# 14871_Schematic.net
KiCad netlist of a schematic drawn in Altium Designer
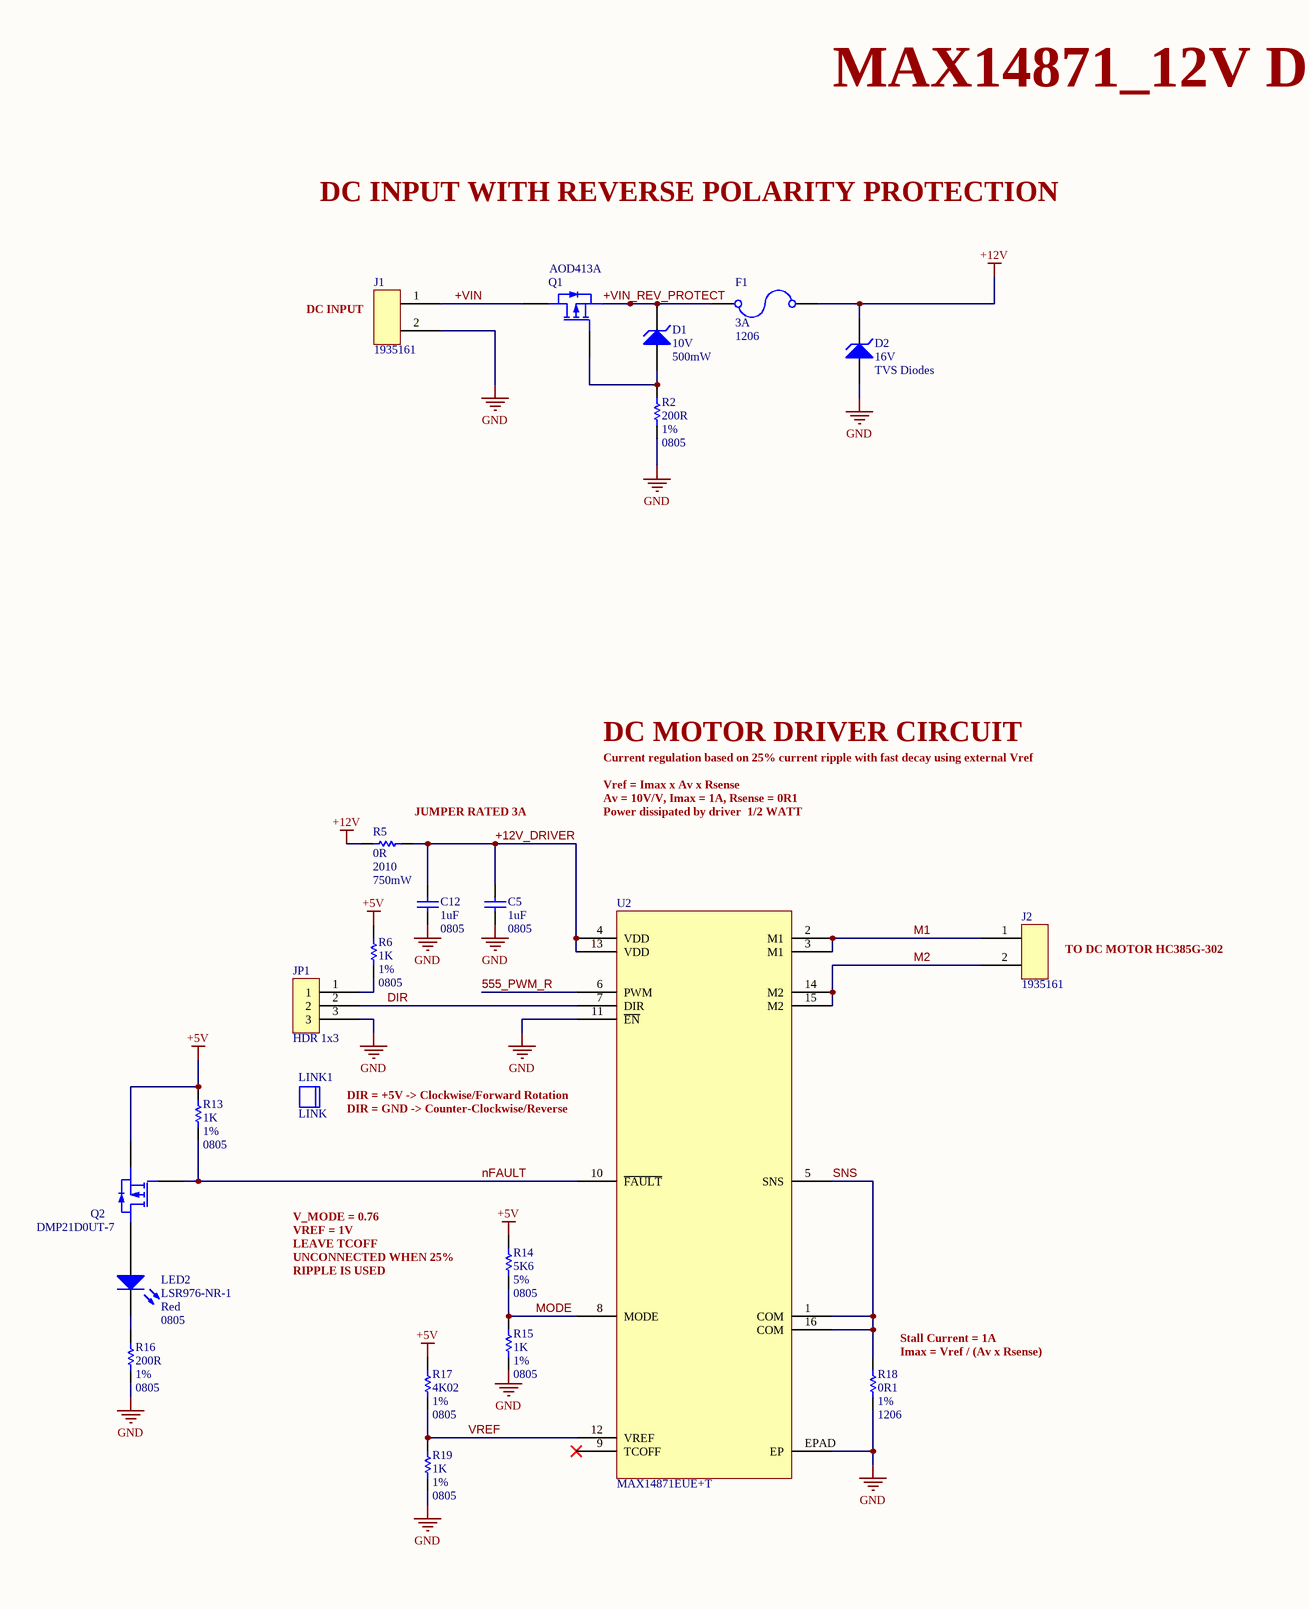
[diagram p0: 14871_Schematic.SchDoc, left]
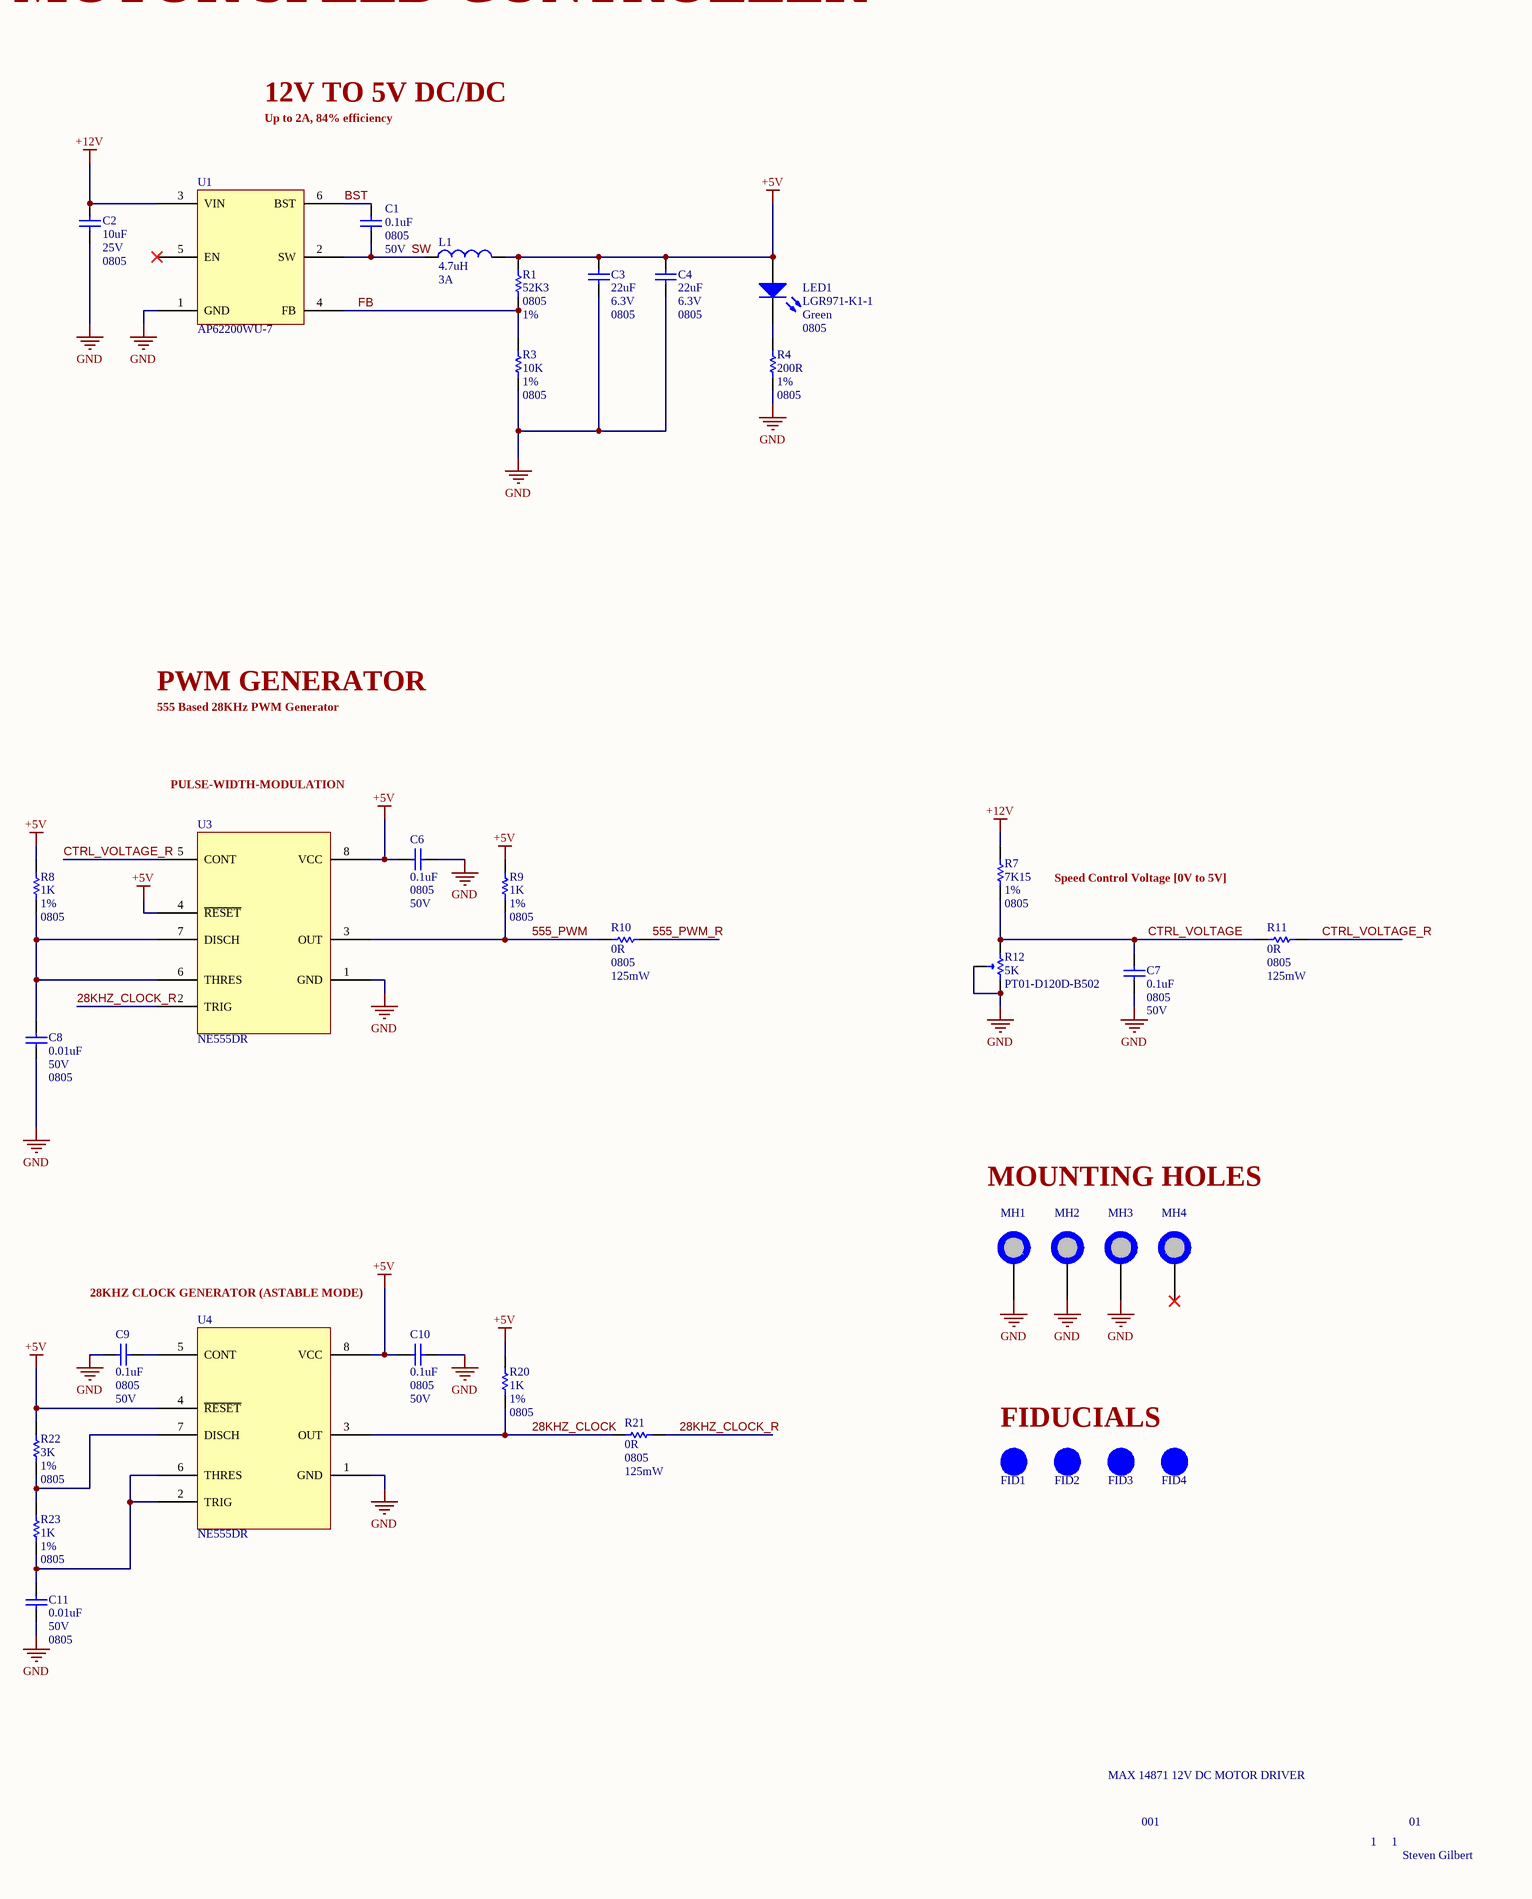
[diagram p1: 14871_Schematic.SchDoc, right]

(export (version "E")
  (design (tool "Eeschema 10.0.6"))
  (components
    (comp (ref "C1")
      (value "0.1uF")
      (footprint "C0805")
      (description "CAP CER 0.1UF X7R 50V 0805  +/-10%; 50WVDC; SMD; 2.5% Df; 0.037IN. ,")
      (fields
        (field (name "MANUFACTURER") "Kyocera AVX")
        (field (name "MANUFACTURER PART NUMBER") "08055C104KAT2A")
        (field (name "CASE CODE (IMPERIAL)") "0805")
        (field (name "VOLTAGE RATING (DC)") "50V")
      )
      (libsource (lib "MAX14871_Project") (part "08055C104KAT2A"))
    )
    (comp (ref "C2")
      (value "10uF")
      (footprint "C0805")
      (description "CAP CER 10UF 25V X5R 0805")
      (fields
        (field (name "MANUFACTURER") "Murata")
        (field (name "MANUFACTURER PART NUMBER") "GRM21BR61E106KA73L")
        (field (name "VOLTAGE RATING (DC)") "25V")
        (field (name "CASE/PACKAGE") "0805")
      )
      (libsource (lib "MAX14871_Project") (part "GRM21BR61E106KA73L"))
    )
    (comp (ref "C3")
      (value "22uF")
      (footprint "C0805")
      (description "CAP CER 6.3V X5R 20% SMD 0805 85°C Embossed T/R")
      (fields
        (field (name "MANUFACTURER") "Samsung")
        (field (name "MANUFACTURER PART NUMBER") "CL21A226MQQNNNG")
        (field (name "VOLTAGE RATING") "6.3V")
        (field (name "CASE/PACKAGE") "0805")
      )
      (libsource (lib "MAX14871_Project") (part "CL21A226MQQNNNG"))
    )
    (comp (ref "C4")
      (value "22uF")
      (footprint "C0805")
      (description "CAP CER 6.3V X5R 20% SMD 0805 85°C Embossed T/R")
      (fields
        (field (name "MANUFACTURER") "Samsung")
        (field (name "MANUFACTURER PART NUMBER") "CL21A226MQQNNNG")
        (field (name "VOLTAGE RATING") "6.3V")
        (field (name "CASE/PACKAGE") "0805")
      )
      (libsource (lib "MAX14871_Project") (part "CL21A226MQQNNNG"))
    )
    (comp (ref "C5")
      (value "1uF")
      (footprint "C0805")
      (description "Cap Cer 1UF 35V X7R 0805")
      (fields
        (field (name "MANUFACTURER") "Kyocera AVX")
        (field (name "MANUFACTURER PART NUMBER") "0805DC105KAT2A")
        (field (name "CASE/PACKAGE") "0805")
      )
      (libsource (lib "MAX14871_Project") (part "0805DC105KAT2A"))
    )
    (comp (ref "C6")
      (value "0.1uF")
      (footprint "C0805")
      (description "CAP CER 0.1UF X7R 50V 0805  +/-10%; 50WVDC; SMD; 2.5% Df; 0.037IN. ,")
      (fields
        (field (name "MANUFACTURER") "Kyocera AVX")
        (field (name "MANUFACTURER PART NUMBER") "08055C104KAT2A")
        (field (name "CASE CODE (IMPERIAL)") "0805")
        (field (name "VOLTAGE RATING (DC)") "50V")
      )
      (libsource (lib "MAX14871_Project") (part "08055C104KAT2A"))
    )
    (comp (ref "C7")
      (value "0.1uF")
      (footprint "C0805")
      (description "CAP CER 0.1UF X7R 50V 0805  +/-10%; 50WVDC; SMD; 2.5% Df; 0.037IN. ,")
      (fields
        (field (name "MANUFACTURER") "Kyocera AVX")
        (field (name "MANUFACTURER PART NUMBER") "08055C104KAT2A")
        (field (name "CASE CODE (IMPERIAL)") "0805")
        (field (name "VOLTAGE RATING (DC)") "50V")
      )
      (libsource (lib "MAX14871_Project") (part "08055C104KAT2A"))
    )
    (comp (ref "C8")
      (value "0.01uF")
      (footprint "C0805")
      (description "CAP CER 0.01uF 50V X7R 10% SMD 0805 125C Plastic T/R")
      (fields
        (field (name "MANUFACTURER") "KEMET")
        (field (name "MANUFACTURER PART NUMBER") "C0805C103K5RACTU")
        (field (name "VOLTAGE RATING") "50V")
        (field (name "CASE/PACKAGE") "0805")
      )
      (libsource (lib "MAX14871_Project") (part "C0805C103K5RACTU"))
    )
    (comp (ref "C9")
      (value "0.1uF")
      (footprint "C0805")
      (description "CAP CER 0.1UF X7R 50V 0805  +/-10%; 50WVDC; SMD; 2.5% Df; 0.037IN. ,")
      (fields
        (field (name "MANUFACTURER") "Kyocera AVX")
        (field (name "MANUFACTURER PART NUMBER") "08055C104KAT2A")
        (field (name "CASE CODE (IMPERIAL)") "0805")
        (field (name "VOLTAGE RATING (DC)") "50V")
      )
      (libsource (lib "MAX14871_Project") (part "08055C104KAT2A"))
    )
    (comp (ref "C10")
      (value "0.1uF")
      (footprint "C0805")
      (description "CAP CER 0.1UF X7R 50V 0805  +/-10%; 50WVDC; SMD; 2.5% Df; 0.037IN. ,")
      (fields
        (field (name "MANUFACTURER") "Kyocera AVX")
        (field (name "MANUFACTURER PART NUMBER") "08055C104KAT2A")
        (field (name "CASE CODE (IMPERIAL)") "0805")
        (field (name "VOLTAGE RATING (DC)") "50V")
      )
      (libsource (lib "MAX14871_Project") (part "08055C104KAT2A"))
    )
    (comp (ref "C11")
      (value "0.01uF")
      (footprint "C0805")
      (description "CAP CER 0.01uF 50V X7R 10% SMD 0805 125C Plastic T/R")
      (fields
        (field (name "MANUFACTURER") "KEMET")
        (field (name "MANUFACTURER PART NUMBER") "C0805C103K5RACTU")
        (field (name "VOLTAGE RATING") "50V")
        (field (name "CASE/PACKAGE") "0805")
      )
      (libsource (lib "MAX14871_Project") (part "C0805C103K5RACTU"))
    )
    (comp (ref "C12")
      (value "1uF")
      (footprint "C0805")
      (description "Cap Cer 1UF 35V X7R 0805")
      (fields
        (field (name "MANUFACTURER") "Kyocera AVX")
        (field (name "MANUFACTURER PART NUMBER") "0805DC105KAT2A")
        (field (name "CASE/PACKAGE") "0805")
      )
      (libsource (lib "MAX14871_Project") (part "0805DC105KAT2A"))
    )
    (comp (ref "D1")
      (value "10V")
      (footprint "SOD123_Zener")
      (description "Vz=10V 9.4V~10.6V Izt=5mA")
      (fields
        (field (name "MANUFACTURER") "Diodes")
        (field (name "TOLERANCE") "6%")
        (field (name "MAX POWER DISSIPATION") "500mW")
      )
      (libsource (lib "MAX14871_Project") (part "BZT52C10-7-F"))
    )
    (comp (ref "D2")
      (value "16V")
      (footprint "TVS_SOD123FL")
      (description "TVS DIODE 16VWM 26VC SOD123FL")
      (fields
        (field (name "MANUFACTURER") "MCC")
        (field (name "MANUFACTURER PART NUMBER") "SMF16A-TP")
        (field (name "CATEGORY") "TVS Diodes")
      )
      (libsource (lib "MAX14871_Project") (part "SMF16A-TP"))
    )
    (comp (ref "F1")
      (value "3A")
      (footprint "FUSE1206")
      (description "Fuse Chip 3A 63V Slow Blow 2-Pin T/R")
      (fields
        (field (name "MANUFACTURER") "Bel")
        (field (name "MANUFACTURER PART NUMBER") "0685T3000-01")
        (field (name "CASE/PACKAGE") "1206")
      )
      (libsource (lib "MAX14871_Project") (part "0685T3000-01"))
    )
    (comp (ref "FID1")
      (value "FID_1MM")
      (footprint "FID_40X120D")
      (description "Fiducial 40mil diameter, 120 Mask")
      (libsource (lib "MAX14871_Project") (part "FID_1mm"))
    )
    (comp (ref "FID2")
      (value "FID_1MM")
      (footprint "FID_40X120D")
      (description "Fiducial 40mil diameter, 120 Mask")
      (libsource (lib "MAX14871_Project") (part "FID_1mm"))
    )
    (comp (ref "FID3")
      (value "FID_1MM")
      (footprint "FID_40X120D")
      (description "Fiducial 40mil diameter, 120 Mask")
      (libsource (lib "MAX14871_Project") (part "FID_1mm"))
    )
    (comp (ref "FID4")
      (value "FID_1MM")
      (footprint "FID_40X120D")
      (description "Fiducial 40mil diameter, 120 Mask")
      (libsource (lib "MAX14871_Project") (part "FID_1mm"))
    )
    (comp (ref "J1")
      (value "1935161")
      (footprint "1935161")
      (description "Conn PC Terminal Block 2 POS 5mm Solder ST Thru-Hole 17.5A")
      (fields (field (name "MANUFACTURER") "Phoenix Contact") (field (name "VOLTAGE") "300V"))
      (libsource (lib "MAX14871_Project") (part "1935161"))
    )
    (comp (ref "J2")
      (value "1935161")
      (footprint "1935161")
      (description "Conn PC Terminal Block 2 POS 5mm Solder ST Thru-Hole 17.5A")
      (fields (field (name "MANUFACTURER") "Phoenix Contact") (field (name "VOLTAGE") "300V"))
      (libsource (lib "") (part "1935161_1"))
    )
    (comp (ref "JP1")
      (value "HDR 1x3")
      (footprint "HDR_1x3_2.54mm")
      (description "CONN HEADER VERT 3POS 2.54MM")
      (libsource (lib "MAX14871_Project") (part "68000-103HLF"))
    )
    (comp (ref "L1")
      (value "4.7uH")
      (footprint "NR6028T4R7M")
      (description "Inductor Power Shielded Wirewound 4.7uH 20% 100KHz Ferrite 3A 0.0403Ohm DCR 2424 T/R")
      (fields
        (field (name "MANUFACTURER") "Taiyo Yuden")
        (field (name "MANUFACTURER PART NUMBER") "NR6028T4R7M")
        (field (name "MAX DC CURRENT") "3A")
      )
      (libsource (lib "MAX14871_Project") (part "NR6028T4R7M"))
    )
    (comp (ref "LED1")
      (value "LGR971-K1-1")
      (footprint "LED0805 - Green")
      (description "LED SMT GREEN 0805")
      (fields (field (name "ILLUMINATION COLOR") "Green") (field (name "CASE/PACKAGE") "0805"))
      (libsource (lib "MAX14871_Project") (part "LGR971-K1-1"))
    )
    (comp (ref "LED2")
      (value "LSR976-NR-1")
      (footprint "LED0805")
      (description "LED SMT RED 0805")
      (fields
        (field (name "MANUFACTURER") "Osram Opto")
        (field (name "ILLUMINATION COLOR") "Red")
        (field (name "CASE/PACKAGE") "0805")
      )
      (libsource (lib "MAX14871_Project") (part "LSR976-NR-1"))
    )
    (comp (ref "LINK1")
      (value "LINK")
      (description "2 Position 2.54 mm Centerline Single Circuit Open Top Jumper")
      (fields
        (field (name "MANUFACTURER") "Sullins")
        (field (name "MANUFACTURER PART NUMBER") "QPC02SXGN-RC")
      )
      (libsource (lib "MAX14871_Project") (part "QPC02SXGN-RC"))
    )
    (comp (ref "MH1")
      (value "MH_7.4MMC_3.2MMD")
      (footprint "MH_7.4MMC_3.2MMD")
      (description "Mounting Hole 7.4mm Diameter, 3.2mm Drill")
      (libsource (lib "MAX14871_Project") (part "MH_7.4MMC_3.2MMD"))
    )
    (comp (ref "MH2")
      (value "MH_7.4MMC_3.2MMD")
      (footprint "MH_7.4MMC_3.2MMD")
      (description "Mounting Hole 7.4mm Diameter, 3.2mm Drill")
      (libsource (lib "MAX14871_Project") (part "MH_7.4MMC_3.2MMD"))
    )
    (comp (ref "MH3")
      (value "MH_7.4MMC_3.2MMD")
      (footprint "MH_7.4MMC_3.2MMD")
      (description "Mounting Hole 7.4mm Diameter, 3.2mm Drill")
      (libsource (lib "MAX14871_Project") (part "MH_7.4MMC_3.2MMD"))
    )
    (comp (ref "MH4")
      (value "MH_7.4MMNC_3.2MMD")
      (footprint "MH_7.4MMD_3.2MMD_NON_COPPER_NPTH")
      (description "Hole 7.4MM Diameter (Non Copper), 3.2mm Drill NPTH")
      (libsource (lib "MAX14871_Project") (part "MH_7.4MMNC_3.2MMD"))
    )
    (comp (ref "Q1")
      (value "AOD413A")
      (footprint "TO252")
      (description "MOSFET P-CH 40V 12A TO252")
      (fields (field (name "MANUFACTURER") "Alpha & Omega Semiconductor"))
      (libsource (lib "MAX14871_Project") (part "AOD413A"))
    )
    (comp (ref "Q2")
      (value "DMP21D0UT-7")
      (footprint "SOT523")
      (description "MOSFET P-CH 20V 0.59A SOT523")
      (fields (field (name "MANUFACTURER") "Diodes"))
      (libsource (lib "MAX14871_Project") (part "DMP21D0UT-7"))
    )
    (comp (ref "R1")
      (value "52K3")
      (footprint "R0805")
      (description "RES SMD 52K3 OHM 1% 1/8W 0805 ±100ppm/°C SMD Paper T/R")
      (fields
        (field (name "MANUFACTURER") "Yageo")
        (field (name "MANUFACTURER PART NUMBER") "RC0805FR-0752K3L")
        (field (name "CASE/PACKAGE") "0805")
        (field (name "TOLERANCE") "1%")
      )
      (libsource (lib "MAX14871_Project") (part "RC0805FR-0752K3L"))
    )
    (comp (ref "R2")
      (value "200R")
      (footprint "R0805")
      (description "RES SMD 200 OHM 1% 1/8W 0805 ±100ppm/°C")
      (fields
        (field (name "MANUFACTURER") "Yageo")
        (field (name "MANUFACTURER PART NUMBER") "RC0805FR-07200RL")
        (field (name "TOLERANCE") "1%")
        (field (name "CASE/PACKAGE") "0805")
      )
      (libsource (lib "MAX14871_Project") (part "RC0805FR-07200RL"))
    )
    (comp (ref "R3")
      (value "10K")
      (footprint "R0805")
      (description "RES SMD 10K OHM 1% 1/8W  0805 Thick Film+/-100ppm/C Epoxy Pad SMD T/R")
      (fields
        (field (name "MANUFACTURER") "Yageo")
        (field (name "MANUFACTURER PART NUMBER") "RC0805FR-0710KL")
        (field (name "TOLERANCE") "1%")
        (field (name "CASE/PACKAGE") "0805")
      )
      (libsource (lib "MAX14871_Project") (part "RC0805FR-0710KL"))
    )
    (comp (ref "R4")
      (value "200R")
      (footprint "R0805")
      (description "RES SMD 200 OHM 1% 1/8W 0805 ±100ppm/°C")
      (fields
        (field (name "MANUFACTURER") "Yageo")
        (field (name "MANUFACTURER PART NUMBER") "RC0805FR-07200RL")
        (field (name "TOLERANCE") "1%")
        (field (name "CASE/PACKAGE") "0805")
      )
      (libsource (lib "MAX14871_Project") (part "RC0805FR-07200RL"))
    )
    (comp (ref "R5")
      (value "0R")
      (footprint "R2010")
      (description "Res Thick Film 2010 0 Ohm Molded SMD Automotive Plastic T/R")
      (fields
        (field (name "MANUFACTURER") "Stackpole Electronics")
        (field (name "MANUFACTURER PART NUMBER") "RMCF2010ZT0R00")
        (field (name "CASE/PACKAGE") "2010")
        (field (name "POWER RATING") "750mW")
      )
      (libsource (lib "MAX14871_Project") (part "RMCF2010ZT0R00"))
    )
    (comp (ref "R6")
      (value "1K")
      (footprint "R0805")
      (description "RES SMD 1K OHM 1% 1/8W 0805")
      (fields
        (field (name "MANUFACTURER") "Yageo")
        (field (name "MANUFACTURER PART NUMBER") "RC0805FR-071KL")
        (field (name "TOLERANCE") "1%")
        (field (name "CASE/PACKAGE") "0805")
      )
      (libsource (lib "MAX14871_Project") (part "RC0805FR-071KL"))
    )
    (comp (ref "R7")
      (value "7K15")
      (footprint "R0805")
      (description "RES SMD 7K15 OHM 1% 1/8W 0805 Thick Film 2.0 x 1.2 mm 100ppm/ C Molded SMD Paper T/R")
      (fields
        (field (name "MANUFACTURER") "Yageo")
        (field (name "MANUFACTURER PART NUMBER") "RC0805FR-077K15L")
        (field (name "TOLERANCE") "1%")
        (field (name "CASE/PACKAGE") "0805")
      )
      (libsource (lib "MAX14871_Project") (part "RC0805FR-077K15L"))
    )
    (comp (ref "R8")
      (value "1K")
      (footprint "R0805")
      (description "RES SMD 1K OHM 1% 1/8W 0805")
      (fields
        (field (name "MANUFACTURER") "Yageo")
        (field (name "MANUFACTURER PART NUMBER") "RC0805FR-071KL")
        (field (name "TOLERANCE") "1%")
        (field (name "CASE/PACKAGE") "0805")
      )
      (libsource (lib "MAX14871_Project") (part "RC0805FR-071KL"))
    )
    (comp (ref "R9")
      (value "1K")
      (footprint "R0805")
      (description "RES SMD 1K OHM 1% 1/8W 0805")
      (fields
        (field (name "MANUFACTURER") "Yageo")
        (field (name "MANUFACTURER PART NUMBER") "RC0805FR-071KL")
        (field (name "TOLERANCE") "1%")
        (field (name "CASE/PACKAGE") "0805")
      )
      (libsource (lib "MAX14871_Project") (part "RC0805FR-071KL"))
    )
    (comp (ref "R10")
      (value "0R")
      (footprint "R0805")
      (description "JUMPER SMD 0 OHM 150V 1/8W 0805")
      (fields
        (field (name "MANUFACTURER") "Yageo")
        (field (name "MANUFACTURER PART NUMBER") "RC0805JR-070RL")
        (field (name "CASE/PACKAGE") "0805")
        (field (name "MAX POWER DISSIPATION") "125mW")
      )
      (libsource (lib "MAX14871_Project") (part "RC0805JR-070RL"))
    )
    (comp (ref "R11")
      (value "0R")
      (footprint "R0805")
      (description "JUMPER SMD 0 OHM 150V 1/8W 0805")
      (fields
        (field (name "MANUFACTURER") "Yageo")
        (field (name "MANUFACTURER PART NUMBER") "RC0805JR-070RL")
        (field (name "CASE/PACKAGE") "0805")
        (field (name "MAX POWER DISSIPATION") "125mW")
      )
      (libsource (lib "MAX14871_Project") (part "RC0805JR-070RL"))
    )
    (comp (ref "R12")
      (value "5K")
      (footprint "TRIM_PT01-D120D-B502")
      (description "POT 5K OHM Panel Mount/Through Hole, Rotary Potentiometer")
      (fields
        (field (name "MANUFACTURER") "CUI Devices")
        (field (name "MANUFACTURER PART NUMBER") "PT01-D120D-B502")
      )
      (libsource (lib "MAX14871_Project") (part "PT01-D120D-B502"))
    )
    (comp (ref "R13")
      (value "1K")
      (footprint "R0805")
      (description "RES SMD 1K OHM 1% 1/8W 0805")
      (fields
        (field (name "MANUFACTURER") "Yageo")
        (field (name "MANUFACTURER PART NUMBER") "RC0805FR-071KL")
        (field (name "TOLERANCE") "1%")
        (field (name "CASE/PACKAGE") "0805")
      )
      (libsource (lib "MAX14871_Project") (part "RC0805FR-071KL"))
    )
    (comp (ref "R14")
      (value "5K6")
      (footprint "R0805")
      (description "RES SMD 5K6 OHM 5% 1/8W 0805  Thick Film ±100ppm/C Pad SMD T/R")
      (fields
        (field (name "MANUFACTURER") "Yageo")
        (field (name "MANUFACTURER PART NUMBER") "RC0805JR-075K6L")
        (field (name "RESISTANCE TOLERANCE") "5%")
        (field (name "CASE/PACKAGE") "0805")
      )
      (libsource (lib "MAX14871_Project") (part "RC0805JR-075K6L"))
    )
    (comp (ref "R15")
      (value "1K")
      (footprint "R0805")
      (description "RES SMD 1K OHM 1% 1/8W 0805")
      (fields
        (field (name "MANUFACTURER") "Yageo")
        (field (name "MANUFACTURER PART NUMBER") "RC0805FR-071KL")
        (field (name "TOLERANCE") "1%")
        (field (name "CASE/PACKAGE") "0805")
      )
      (libsource (lib "MAX14871_Project") (part "RC0805FR-071KL"))
    )
    (comp (ref "R16")
      (value "200R")
      (footprint "R0805")
      (description "RES SMD 200 OHM 1% 1/8W 0805 ±100ppm/°C")
      (fields
        (field (name "MANUFACTURER") "Yageo")
        (field (name "MANUFACTURER PART NUMBER") "RC0805FR-07200RL")
        (field (name "TOLERANCE") "1%")
        (field (name "CASE/PACKAGE") "0805")
      )
      (libsource (lib "MAX14871_Project") (part "RC0805FR-07200RL"))
    )
    (comp (ref "R17")
      (value "4K02")
      (footprint "R0805")
      (description "RES SMD 4K02 OHM 1% 1/8W 0805 Thick Film 2.0 x 1.2 mm 100ppm/ C Molded SMD Paper T/R")
      (fields
        (field (name "MANUFACTURER") "Yageo")
        (field (name "MANUFACTURER PART NUMBER") "RC0805FR-074K02L")
        (field (name "TOLERANCE") "1%")
        (field (name "CASE/PACKAGE") "0805")
      )
      (libsource (lib "MAX14871_Project") (part "RC0805FR-074K02L"))
    )
    (comp (ref "R18")
      (value "0R1")
      (footprint "R1206")
      (description "RES SENSE SMD 0R1 OHM 1% 1W 1206")
      (fields
        (field (name "MANUFACTURER") "Cyntec")
        (field (name "MANUFACTURER PART NUMBER") "VSRP1206S1-R100F")
        (field (name "TOLERANCE") "1%")
        (field (name "PACKAGE") "1206")
      )
      (libsource (lib "MAX14871_Project") (part "VSRP1206S1-R100F"))
    )
    (comp (ref "R19")
      (value "1K")
      (footprint "R0805")
      (description "RES SMD 1K OHM 1% 1/8W 0805")
      (fields
        (field (name "MANUFACTURER") "Yageo")
        (field (name "MANUFACTURER PART NUMBER") "RC0805FR-071KL")
        (field (name "TOLERANCE") "1%")
        (field (name "CASE/PACKAGE") "0805")
      )
      (libsource (lib "MAX14871_Project") (part "RC0805FR-071KL"))
    )
    (comp (ref "R20")
      (value "1K")
      (footprint "R0805")
      (description "RES SMD 1K OHM 1% 1/8W 0805")
      (fields
        (field (name "MANUFACTURER") "Yageo")
        (field (name "MANUFACTURER PART NUMBER") "RC0805FR-071KL")
        (field (name "TOLERANCE") "1%")
        (field (name "CASE/PACKAGE") "0805")
      )
      (libsource (lib "MAX14871_Project") (part "RC0805FR-071KL"))
    )
    (comp (ref "R21")
      (value "0R")
      (footprint "R0805")
      (description "JUMPER SMD 0 OHM 150V 1/8W 0805")
      (fields
        (field (name "MANUFACTURER") "Yageo")
        (field (name "MANUFACTURER PART NUMBER") "RC0805JR-070RL")
        (field (name "CASE/PACKAGE") "0805")
        (field (name "MAX POWER DISSIPATION") "125mW")
      )
      (libsource (lib "MAX14871_Project") (part "RC0805JR-070RL"))
    )
    (comp (ref "R22")
      (value "3K")
      (footprint "R0805")
      (description "RES SMD 3K OHM 1% 1/8W 0805 Thick Film ±100ppm/C Pad SMD T/R")
      (fields
        (field (name "MANUFACTURER") "Yageo")
        (field (name "MANUFACTURER PART NUMBER") "RC0805FR-073KL")
        (field (name "TOLERANCE") "1%")
        (field (name "CASE/PACKAGE") "0805")
      )
      (libsource (lib "MAX14871_Project") (part "RC0805FR-073KL"))
    )
    (comp (ref "R23")
      (value "1K")
      (footprint "R0805")
      (description "RES SMD 1K OHM 1% 1/8W 0805")
      (fields
        (field (name "MANUFACTURER") "Yageo")
        (field (name "MANUFACTURER PART NUMBER") "RC0805FR-071KL")
        (field (name "TOLERANCE") "1%")
        (field (name "CASE/PACKAGE") "0805")
      )
      (libsource (lib "MAX14871_Project") (part "RC0805FR-071KL"))
    )
    (comp (ref "U1")
      (value "AP62200WU-7")
      (footprint "TSOT26")
      (description "4.2V to 18V Input 2A Low IQ Synchronous Buck Converter 6-Pin TSOT-26 T/R")
      (fields (field (name "MANUFACTURER") "Diodes"))
      (libsource (lib "MAX14871_Project") (part "AP62200WU-7"))
    )
    (comp (ref "U2")
      (value "MAX14871EUE+T")
      (footprint "21-0108_U16E+3_MXM-M")
      (description "IC Motor Driver 4.5V-36V 16TSSOP")
      (fields (field (name "MANUFACTURER") "Analog Devices"))
      (libsource (lib "MAX14871_Project") (part "MAX14871EUE+T"))
    )
    (comp (ref "U3")
      (value "NE555DR")
      (footprint "8-SOIC")
      (description "IC OSC SGL TIMER 100KHZ 8-SOIC")
      (fields (field (name "MANUFACTURER") "Texas Instruments"))
      (libsource (lib "MAX14871_Project") (part "NE555DR"))
    )
    (comp (ref "U4")
      (value "NE555DR")
      (footprint "8-SOIC")
      (description "IC OSC SGL TIMER 100KHZ 8-SOIC")
      (fields (field (name "MANUFACTURER") "Texas Instruments"))
      (libsource (lib "MAX14871_Project") (part "NE555DR"))
    )
  )
  (nets
    (net (code "1") (name "+5V") (class "Default")
      (node (ref "C10") (pin "1") (pinfunction "1_1") (pintype "passive"))
      (node (ref "C3") (pin "2") (pinfunction "2_2") (pintype "passive"))
      (node (ref "C4") (pin "2") (pinfunction "2_2") (pintype "passive"))
      (node (ref "C6") (pin "1") (pinfunction "1_1") (pintype "passive"))
      (node (ref "L1") (pin "2") (pinfunction "2_2") (pintype "passive"))
      (node (ref "LED1") (pin "A") (pinfunction "A_A") (pintype "passive"))
      (node (ref "Q2") (pin "S") (pinfunction "S_S") (pintype "passive"))
      (node (ref "R1") (pin "1") (pinfunction "1_1") (pintype "passive"))
      (node (ref "R13") (pin "1") (pinfunction "1_1") (pintype "passive"))
      (node (ref "R14") (pin "1") (pinfunction "1_1") (pintype "passive"))
      (node (ref "R17") (pin "1") (pinfunction "1_1") (pintype "passive"))
      (node (ref "R20") (pin "1") (pinfunction "1_1") (pintype "passive"))
      (node (ref "R22") (pin "1") (pinfunction "1_1") (pintype "passive"))
      (node (ref "R6") (pin "1") (pinfunction "1_1") (pintype "passive"))
      (node (ref "R8") (pin "1") (pinfunction "1_1") (pintype "passive"))
      (node (ref "R9") (pin "1") (pinfunction "1_1") (pintype "passive"))
      (node (ref "U3") (pin "4") (pinfunction "~{RESET}_4") (pintype "passive"))
      (node (ref "U3") (pin "8") (pinfunction "VCC_8") (pintype "passive"))
      (node (ref "U4") (pin "4") (pinfunction "~{RESET}_4") (pintype "passive"))
      (node (ref "U4") (pin "8") (pinfunction "VCC_8") (pintype "passive"))
    )
    (net (code "2") (name "+12V") (class "Default")
      (node (ref "C2") (pin "2") (pinfunction "2_2") (pintype "passive"))
      (node (ref "D2") (pin "K") (pinfunction "K_K") (pintype "passive"))
      (node (ref "F1") (pin "2") (pinfunction "2_2") (pintype "passive"))
      (node (ref "R5") (pin "2") (pinfunction "2_2") (pintype "passive"))
      (node (ref "R7") (pin "1") (pinfunction "1_1") (pintype "passive"))
      (node (ref "U1") (pin "3") (pinfunction "VIN_3") (pintype "passive"))
    )
    (net (code "3") (name "/+12V_DRIVER") (class "Default")
      (node (ref "C12") (pin "2") (pinfunction "2_2") (pintype "passive"))
      (node (ref "C5") (pin "2") (pinfunction "2_2") (pintype "passive"))
      (node (ref "R5") (pin "1") (pinfunction "1_1") (pintype "passive"))
      (node (ref "U2") (pin "13") (pinfunction "VDD_13") (pintype "passive"))
      (node (ref "U2") (pin "4") (pinfunction "VDD_4") (pintype "passive"))
    )
    (net (code "4") (name "/+VIN") (class "Default")
      (node (ref "J1") (pin "1") (pinfunction "1_1") (pintype "passive"))
      (node (ref "Q1") (pin "D") (pinfunction "D_D") (pintype "passive"))
    )
    (net (code "5") (name "/+VIN_REV_PROTECT") (class "Default")
      (node (ref "D1") (pin "K") (pinfunction "K_K") (pintype "passive"))
      (node (ref "F1") (pin "1") (pinfunction "1_1") (pintype "passive"))
      (node (ref "Q1") (pin "S") (pinfunction "S_S") (pintype "passive"))
    )
    (net (code "6") (name "/28KHZ_CLOCK") (class "Default")
      (node (ref "R20") (pin "2") (pinfunction "2_2") (pintype "passive"))
      (node (ref "R21") (pin "2") (pinfunction "2_2") (pintype "passive"))
      (node (ref "U4") (pin "3") (pinfunction "OUT_3") (pintype "passive"))
    )
    (net (code "7") (name "/28KHZ_CLOCK_R") (class "Default")
      (node (ref "R21") (pin "1") (pinfunction "1_1") (pintype "passive"))
      (node (ref "U3") (pin "2") (pinfunction "TRIG_2") (pintype "passive"))
    )
    (net (code "8") (name "/555_PWM") (class "Default")
      (node (ref "R10") (pin "2") (pinfunction "2_2") (pintype "passive"))
      (node (ref "R9") (pin "2") (pinfunction "2_2") (pintype "passive"))
      (node (ref "U3") (pin "3") (pinfunction "OUT_3") (pintype "passive"))
    )
    (net (code "9") (name "/555_PWM_R") (class "Default")
      (node (ref "R10") (pin "1") (pinfunction "1_1") (pintype "passive"))
      (node (ref "U2") (pin "6") (pinfunction "PWM_6") (pintype "passive"))
    )
    (net (code "10") (name "/BST") (class "Default")
      (node (ref "C1") (pin "2") (pinfunction "2_2") (pintype "passive"))
      (node (ref "U1") (pin "6") (pinfunction "BST_6") (pintype "passive"))
    )
    (net (code "11") (name "/CTRL_VOLTAGE") (class "Default")
      (node (ref "C7") (pin "2") (pinfunction "2_2") (pintype "passive"))
      (node (ref "R11") (pin "2") (pinfunction "2_2") (pintype "passive"))
      (node (ref "R12") (pin "3") (pinfunction "3_3") (pintype "passive"))
      (node (ref "R7") (pin "2") (pinfunction "2_2") (pintype "passive"))
    )
    (net (code "12") (name "/CTRL_VOLTAGE_R") (class "Default")
      (node (ref "R11") (pin "1") (pinfunction "1_1") (pintype "passive"))
      (node (ref "U3") (pin "5") (pinfunction "CONT_5") (pintype "passive"))
    )
    (net (code "13") (name "/DIR") (class "Default")
      (node (ref "JP1") (pin "2") (pinfunction "2_2") (pintype "passive"))
      (node (ref "U2") (pin "7") (pinfunction "DIR_7") (pintype "passive"))
    )
    (net (code "14") (name "/FB") (class "Default")
      (node (ref "R1") (pin "2") (pinfunction "2_2") (pintype "passive"))
      (node (ref "R3") (pin "1") (pinfunction "1_1") (pintype "passive"))
      (node (ref "U1") (pin "4") (pinfunction "FB_4") (pintype "passive"))
    )
    (net (code "15") (name "/M1") (class "Default")
      (node (ref "J2") (pin "1") (pinfunction "1_1") (pintype "passive"))
      (node (ref "U2") (pin "2") (pinfunction "M1_2") (pintype "passive"))
      (node (ref "U2") (pin "3") (pinfunction "M1_3") (pintype "passive"))
    )
    (net (code "16") (name "/M2") (class "Default")
      (node (ref "J2") (pin "2") (pinfunction "2_2") (pintype "passive"))
      (node (ref "U2") (pin "14") (pinfunction "M2_14") (pintype "passive"))
      (node (ref "U2") (pin "15") (pinfunction "M2_15") (pintype "passive"))
    )
    (net (code "17") (name "/MODE") (class "Default")
      (node (ref "R14") (pin "2") (pinfunction "2_2") (pintype "passive"))
      (node (ref "R15") (pin "1") (pinfunction "1_1") (pintype "passive"))
      (node (ref "U2") (pin "8") (pinfunction "MODE_8") (pintype "passive"))
    )
    (net (code "18") (name "/SNS") (class "Default")
      (node (ref "R18") (pin "1") (pinfunction "1_1") (pintype "passive"))
      (node (ref "U2") (pin "1") (pinfunction "COM_1") (pintype "passive"))
      (node (ref "U2") (pin "16") (pinfunction "COM_16") (pintype "passive"))
      (node (ref "U2") (pin "5") (pinfunction "SNS_5") (pintype "passive"))
    )
    (net (code "19") (name "/SW") (class "Default")
      (node (ref "C1") (pin "1") (pinfunction "1_1") (pintype "passive"))
      (node (ref "L1") (pin "1") (pinfunction "1_1") (pintype "passive"))
      (node (ref "U1") (pin "2") (pinfunction "SW_2") (pintype "passive"))
    )
    (net (code "20") (name "/VREF") (class "Default")
      (node (ref "R17") (pin "2") (pinfunction "2_2") (pintype "passive"))
      (node (ref "R19") (pin "1") (pinfunction "1_1") (pintype "passive"))
      (node (ref "U2") (pin "12") (pinfunction "VREF_12") (pintype "passive"))
    )
    (net (code "21") (name "/nFAULT") (class "Default")
      (node (ref "Q2") (pin "G") (pinfunction "G_G") (pintype "passive"))
      (node (ref "R13") (pin "2") (pinfunction "2_2") (pintype "passive"))
      (node (ref "U2") (pin "10") (pinfunction "~{FAULT}_10") (pintype "passive"))
    )
    (net (code "22") (name "GND") (class "Default")
      (node (ref "C10") (pin "2") (pinfunction "2_2") (pintype "passive"))
      (node (ref "C11") (pin "1") (pinfunction "1_1") (pintype "passive"))
      (node (ref "C12") (pin "1") (pinfunction "1_1") (pintype "passive"))
      (node (ref "C2") (pin "1") (pinfunction "1_1") (pintype "passive"))
      (node (ref "C3") (pin "1") (pinfunction "1_1") (pintype "passive"))
      (node (ref "C4") (pin "1") (pinfunction "1_1") (pintype "passive"))
      (node (ref "C5") (pin "1") (pinfunction "1_1") (pintype "passive"))
      (node (ref "C6") (pin "2") (pinfunction "2_2") (pintype "passive"))
      (node (ref "C7") (pin "1") (pinfunction "1_1") (pintype "passive"))
      (node (ref "C8") (pin "1") (pinfunction "1_1") (pintype "passive"))
      (node (ref "C9") (pin "1") (pinfunction "1_1") (pintype "passive"))
      (node (ref "D2") (pin "A") (pinfunction "A_A") (pintype "passive"))
      (node (ref "J1") (pin "2") (pinfunction "2_2") (pintype "passive"))
      (node (ref "JP1") (pin "3") (pinfunction "3_3") (pintype "passive"))
      (node (ref "MH1") (pin "1") (pinfunction "1_1") (pintype "passive"))
      (node (ref "MH2") (pin "1") (pinfunction "1_1") (pintype "passive"))
      (node (ref "MH3") (pin "1") (pinfunction "1_1") (pintype "passive"))
      (node (ref "R12") (pin "1") (pinfunction "1_1") (pintype "passive"))
      (node (ref "R12") (pin "2") (pinfunction "2_2") (pintype "passive"))
      (node (ref "R15") (pin "2") (pinfunction "2_2") (pintype "passive"))
      (node (ref "R16") (pin "2") (pinfunction "2_2") (pintype "passive"))
      (node (ref "R18") (pin "2") (pinfunction "2_2") (pintype "passive"))
      (node (ref "R19") (pin "2") (pinfunction "2_2") (pintype "passive"))
      (node (ref "R2") (pin "2") (pinfunction "2_2") (pintype "passive"))
      (node (ref "R3") (pin "2") (pinfunction "2_2") (pintype "passive"))
      (node (ref "R4") (pin "2") (pinfunction "2_2") (pintype "passive"))
      (node (ref "U1") (pin "1") (pinfunction "GND_1") (pintype "passive"))
      (node (ref "U2") (pin "11") (pinfunction "~{EN}_11") (pintype "passive"))
      (node (ref "U2") (pin "EPAD") (pinfunction "EP_EPAD") (pintype "passive"))
      (node (ref "U3") (pin "1") (pinfunction "GND_1") (pintype "passive"))
      (node (ref "U4") (pin "1") (pinfunction "GND_1") (pintype "passive"))
    )
    (net (code "23") (name "Net-(D1-PadA)") (class "Default")
      (node (ref "D1") (pin "A") (pinfunction "A_A") (pintype "passive"))
      (node (ref "Q1") (pin "G") (pinfunction "G_G") (pintype "passive"))
      (node (ref "R2") (pin "1") (pinfunction "1_1") (pintype "passive"))
    )
    (net (code "24") (name "Net-(JP1-Pad1)") (class "Default")
      (node (ref "JP1") (pin "1") (pinfunction "1_1") (pintype "passive"))
      (node (ref "R6") (pin "2") (pinfunction "2_2") (pintype "passive"))
    )
    (net (code "25") (name "Net-(LED1-PadK)") (class "Default")
      (node (ref "LED1") (pin "K") (pinfunction "K_K") (pintype "passive"))
      (node (ref "R4") (pin "1") (pinfunction "1_1") (pintype "passive"))
    )
    (net (code "26") (name "Net-(LED2-PadA)") (class "Default")
      (node (ref "LED2") (pin "A") (pinfunction "A_A") (pintype "passive"))
      (node (ref "Q2") (pin "D") (pinfunction "D_D") (pintype "passive"))
    )
    (net (code "27") (name "Net-(LED2-PadK)") (class "Default")
      (node (ref "LED2") (pin "K") (pinfunction "K_K") (pintype "passive"))
      (node (ref "R16") (pin "1") (pinfunction "1_1") (pintype "passive"))
    )
    (net (code "28") (name "Net-(U3-DISCH)") (class "Default")
      (node (ref "C8") (pin "2") (pinfunction "2_2") (pintype "passive"))
      (node (ref "R8") (pin "2") (pinfunction "2_2") (pintype "passive"))
      (node (ref "U3") (pin "6") (pinfunction "THRES_6") (pintype "passive"))
      (node (ref "U3") (pin "7") (pinfunction "DISCH_7") (pintype "passive"))
    )
    (net (code "29") (name "Net-(U4-CONT)") (class "Default")
      (node (ref "C9") (pin "2") (pinfunction "2_2") (pintype "passive"))
      (node (ref "U4") (pin "5") (pinfunction "CONT_5") (pintype "passive"))
    )
    (net (code "30") (name "Net-(U4-DISCH)") (class "Default")
      (node (ref "R22") (pin "2") (pinfunction "2_2") (pintype "passive"))
      (node (ref "R23") (pin "1") (pinfunction "1_1") (pintype "passive"))
      (node (ref "U4") (pin "7") (pinfunction "DISCH_7") (pintype "passive"))
    )
    (net (code "31") (name "Net-(U4-THRES)") (class "Default")
      (node (ref "C11") (pin "2") (pinfunction "2_2") (pintype "passive"))
      (node (ref "R23") (pin "2") (pinfunction "2_2") (pintype "passive"))
      (node (ref "U4") (pin "2") (pinfunction "TRIG_2") (pintype "passive"))
      (node (ref "U4") (pin "6") (pinfunction "THRES_6") (pintype "passive"))
    )
    (net (code "32") (name "unconnected-(MH4-Pad1)") (class "Default")
      (node (ref "MH4") (pin "1") (pinfunction "1_1") (pintype "passive+no_connect"))
    )
    (net (code "33") (name "unconnected-(U1-EN-Pad5)") (class "Default")
      (node (ref "U1") (pin "5") (pinfunction "EN_5") (pintype "passive+no_connect"))
    )
    (net (code "34") (name "unconnected-(U2-TCOFF-Pad9)") (class "Default")
      (node (ref "U2") (pin "9") (pinfunction "TCOFF_9") (pintype "passive+no_connect"))
    )
  )
)
